# Main_Pyro.net
KiCad netlist of a schematic drawn in Altium Designer
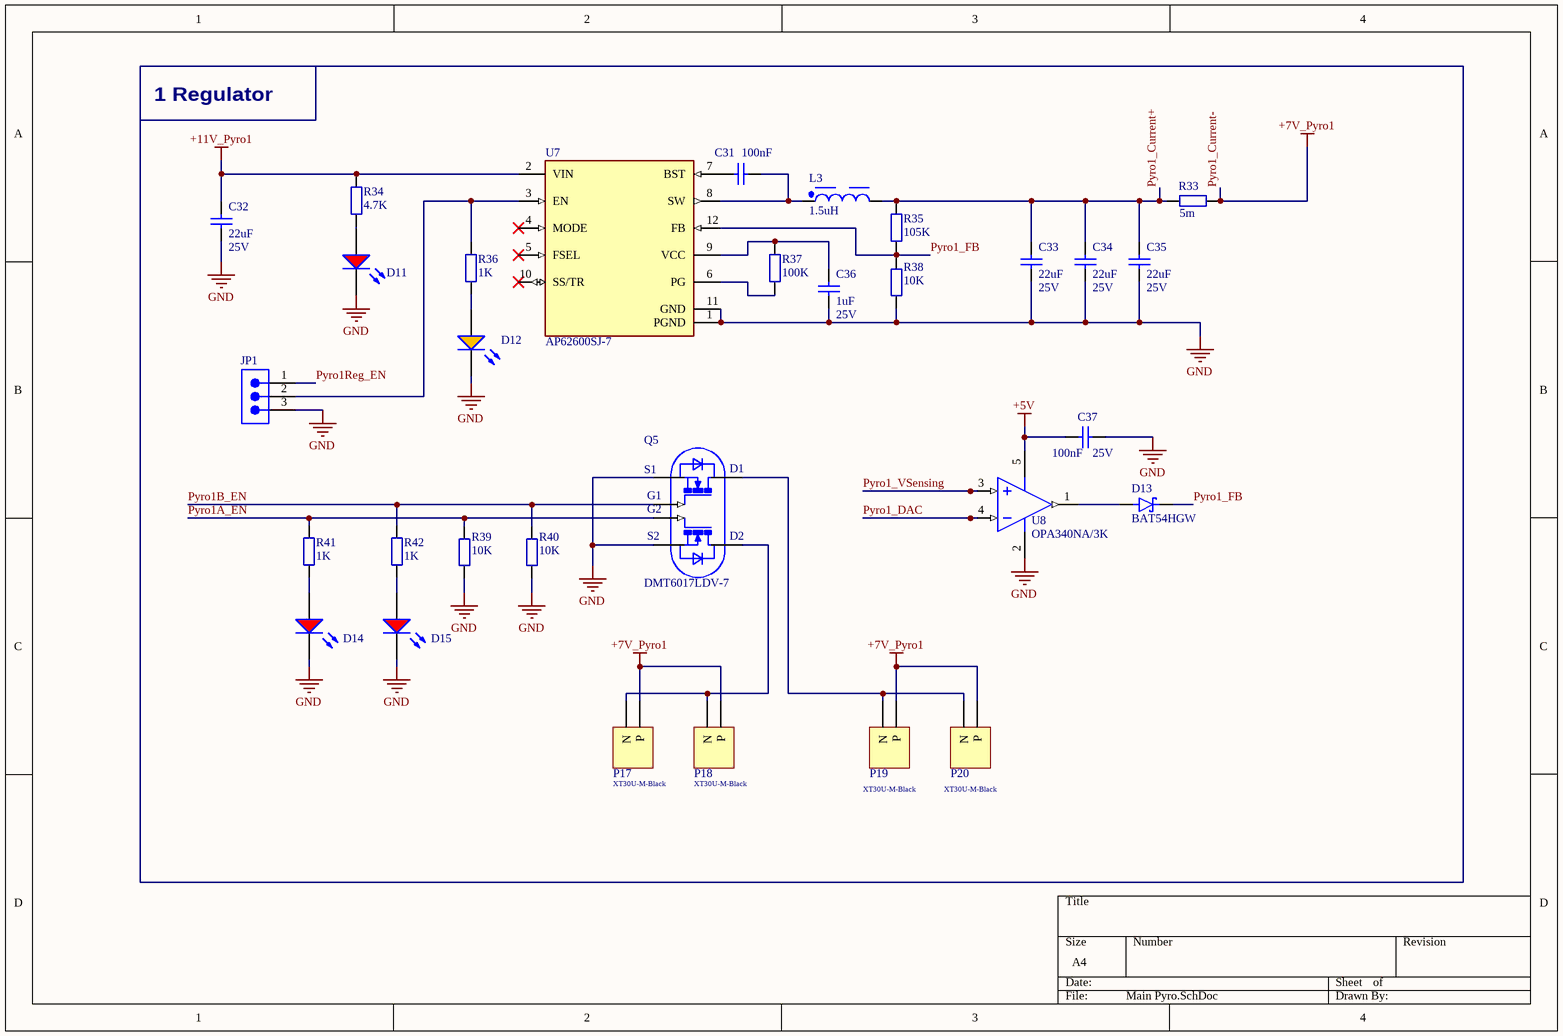
[diagram p0: Main Pyro.SchDoc]

(export (version "E")
  (design (tool "Eeschema 10.0.6"))
  (components
    (comp (ref "C31")
      (value "100nF")
      (footprint "MY_0603")
      (description "Capacitor, 100nF, 0603, 25V")
      (fields (field (name "VOLTAGE") "25V") (field (name "MANUFACTURER") "Wurth Elektronik"))
      (libsource (lib "LEEM UPM") (part "Cap ceramic"))
    )
    (comp (ref "C32")
      (value "22uF")
      (footprint "MY_0805")
      (description "Capacitor, 22uF, 0805, 25V")
      (fields
        (field (name "MANUFACTURER") "Samsung")
        (field (name "MANUFACTURER PART NUMBER") "CL21A226MAYNNNE")
        (field (name "VOLTAGE") "25V")
      )
      (libsource (lib "LEEM UPM") (part "Cap ceramic"))
    )
    (comp (ref "C33")
      (value "22uF")
      (footprint "MY_0805")
      (description "Capacitor, 22uF, 0805, 25V")
      (fields
        (field (name "MANUFACTURER") "Samsung")
        (field (name "MANUFACTURER PART NUMBER") "CL21A226MAYNNNE")
        (field (name "VOLTAGE") "25V")
      )
      (libsource (lib "LEEM UPM") (part "Cap ceramic"))
    )
    (comp (ref "C34")
      (value "22uF")
      (footprint "MY_0805")
      (description "Capacitor, 22uF, 0805, 25V")
      (fields
        (field (name "MANUFACTURER") "Samsung")
        (field (name "MANUFACTURER PART NUMBER") "CL21A226MAYNNNE")
        (field (name "VOLTAGE") "25V")
      )
      (libsource (lib "LEEM UPM") (part "Cap ceramic"))
    )
    (comp (ref "C35")
      (value "22uF")
      (footprint "MY_0805")
      (description "Capacitor, 22uF, 0805, 25V")
      (fields
        (field (name "MANUFACTURER") "Samsung")
        (field (name "MANUFACTURER PART NUMBER") "CL21A226MAYNNNE")
        (field (name "VOLTAGE") "25V")
      )
      (libsource (lib "LEEM UPM") (part "Cap ceramic"))
    )
    (comp (ref "C36")
      (value "1uF")
      (footprint "MY_0603")
      (description "Capacitor, 1uF, 0603, 25V")
      (fields
        (field (name "VOLTE") "25V")
        (field (name "MANUFACTURER") "Wurth Elektronik")
        (field (name "MANUFACTURER PART NUMBER") "885012206052")
      )
      (libsource (lib "LEEM UPM") (part "Cap ceramic"))
    )
    (comp (ref "C37")
      (value "100nF")
      (footprint "MY_0603")
      (description "Capacitor, 100nF, 0603, 25V")
      (fields
        (field (name "VOLTAGE") "25V")
        (field (name "MANUFACTURER") "Wurth Elektronik")
        (field (name "MANUFACTURER PART NUMBER") "885012206071")
      )
      (libsource (lib "LEEM UPM") (part "Cap ceramic"))
    )
    (comp (ref "D11")
      (value "150080RS75000")
      (footprint "WL-SMCW_0805_150080xx75000")
      (description "LED, 0805, Red")
      (fields (field (name "MANUFACTURER") "Wurth Elektronik"))
      (libsource (lib "Altium Content Vault") (part "LED_Red_2A-1K"))
    )
    (comp (ref "D12")
      (value "150080AS75000")
      (footprint "WL-SMCW_0805_150080xx75000")
      (description "LED, 0805, Amber")
      (fields (field (name "MANUFACTURER") "Wurth Elektronik"))
      (libsource (lib "Altium Content Vault") (part "LED_Amber_2A-1K"))
    )
    (comp (ref "D13")
      (value "BAT54HGW")
      (footprint "BAT54HGW-Footprint-1")
      (description "BAT54HGW Schotty Diode")
      (fields (field (name "MANUFACTURER") "Nexperia"))
      (libsource (lib "LEEM UPM") (part "BAT54HGW"))
    )
    (comp (ref "D14")
      (value "150080RS75000")
      (footprint "WL-SMCW_0805_150080xx75000")
      (fields (field (name "MANUFACTURER") "Wurth Elektronik"))
      (libsource (lib "Altium Content Vault") (part "LED_Red_2A-1K"))
    )
    (comp (ref "D15")
      (value "150080RS75000")
      (footprint "WL-SMCW_0805_150080xx75000")
      (fields (field (name "MANUFACTURER") "Wurth Elektronik"))
      (libsource (lib "Altium Content Vault") (part "LED_Red_2A-1K"))
    )
    (comp (ref "JP1")
      (value "Jumper 3 pin, 2,54mm")
      (footprint "Jumper 3 pin, 2,54mm-Footprint-1")
      (libsource (lib "LEEM UPM") (part "New symbol 1"))
    )
    (comp (ref "L3")
      (value "1.5uH")
      (footprint "WE-MAPI_4020")
      (description "74438356015 Fixed Ind 1.5UH 5.8A 19 Mohm SMD")
      (fields
        (field (name "MANUFACTURER") "Wurth Elektronik")
        (field (name "MANUFACTURER PART NUMBER") "74438356015")
      )
      (libsource (lib "Altium Content Vault") (part "Inductor - 2"))
    )
    (comp (ref "P17")
      (value "XT30U-M-Black")
      (footprint "XT30-Footprint-2")
      (description "XT30PW-M公头 Socket,DCsupply,XT30,male,PIN:2")
      (fields (field (name "MANUFACTURER") "AMASS"))
      (libsource (lib "LEEM UPM") (part "XT30PW"))
    )
    (comp (ref "P18")
      (value "XT30U-M-Black")
      (footprint "XT30-Footprint-2")
      (description "XT30PW-M公头 Socket,DCsupply,XT30,male,PIN:2")
      (fields (field (name "MANUFACTURER") "AMASS"))
      (libsource (lib "LEEM UPM") (part "XT30PW"))
    )
    (comp (ref "P19")
      (value "XT30U-M-Black")
      (footprint "XT30-Footprint-2")
      (description "XT30PW-M公头 Socket,DCsupply,XT30,male,PIN:2")
      (fields (field (name "MANUFACTURER") "AMASS"))
      (libsource (lib "LEEM UPM") (part "XT30PW"))
    )
    (comp (ref "P20")
      (value "XT30U-M-Black")
      (footprint "XT30-Footprint-2")
      (description "XT30PW-M公头 Socket,DCsupply,XT30,male,PIN:2")
      (fields (field (name "MANUFACTURER") "AMASS"))
      (libsource (lib "LEEM UPM") (part "XT30PW"))
    )
    (comp (ref "Q5")
      (value "DMT6017LDV-7")
      (footprint "DMT6017LDV-7-Footprint-1")
      (description "Small Signal Field-Effect Transistor")
      (libsource (lib "LEEM UPM") (part "DMT6017LDV"))
    )
    (comp (ref "R33")
      (value "5m")
      (footprint "R0612")
      (description "Resistor, 5m, 0612, 2W")
      (fields
        (field (name "MANUFACTURER") "Vishay")
        (field (name "MANUFACTURER PART NUMBER") "WFCP06125L000FE66")
      )
      (libsource (lib "LEEM UPM") (part "RK73H2ALTD1004F"))
    )
    (comp (ref "R34")
      (value "4.7K")
      (footprint "R0603-0.45")
      (description "Resistor, 4.7K, 0603, 0.1W")
      (fields (field (name "MANUFACTURER") "Wurth") (field (name "MANUFACTURER PART NUMBER") "560112116006"))
      (libsource (lib "LEEM UPM") (part "RK73H2ALTD1004F"))
    )
    (comp (ref "R35")
      (value "105K")
      (footprint "R0603-0.45")
      (description "Resistor, 105K, 0603, 0.1W")
      (fields (field (name "MANUFACTURER") "Wurth") (field (name "MANUFACTURER PART NUMBER") "560112110183"))
      (libsource (lib "IFS_Altium") (part "R"))
    )
    (comp (ref "R36")
      (value "1K")
      (footprint "R0603-0.45")
      (description "Resistor, 1K, 0603, 0.1W")
      (fields (field (name "MANUFACTURER") "Wurth") (field (name "MANUFACTURER PART NUMBER") "560112116014"))
      (libsource (lib "LEEM UPM") (part "RK73H2ALTD1004F"))
    )
    (comp (ref "R37")
      (value "100K")
      (footprint "R0603-0.45")
      (description "Resistor, 100K, 0603, 0.1W")
      (fields (field (name "MANUFACTURER") "Wurth") (field (name "MANUFACTURER PART NUMBER") "560112116004"))
      (libsource (lib "IFS_Altium") (part "R"))
    )
    (comp (ref "R38")
      (value "10K")
      (footprint "R0603-0.45")
      (description "Resistor, 10K, 0603, 0.1W")
      (fields
        (field (name "MANUFACTURER") "Vishay")
        (field (name "MANUFACTURER PART NUMBER") "RCS060310K0FKEA")
      )
      (libsource (lib "IFS_Altium") (part "R"))
    )
    (comp (ref "R39")
      (value "10K")
      (footprint "R0603-0.45")
      (description "Resistor, 10K, 0603, 0.1W")
      (fields
        (field (name "MANUFACTURER") "Vishay")
        (field (name "MANUFACTURER PART NUMBER") "RCS060310K0FKEA")
      )
      (libsource (lib "IFS_Altium") (part "R"))
    )
    (comp (ref "R40")
      (value "10K")
      (footprint "R0603-0.45")
      (description "Resistor, 10K, 0603, 0.1W")
      (fields
        (field (name "MANUFACTURER") "Vishay")
        (field (name "MANUFACTURER PART NUMBER") "RCS060310K0FKEA")
      )
      (libsource (lib "IFS_Altium") (part "R"))
    )
    (comp (ref "R41")
      (value "1K")
      (footprint "R0603-0.45")
      (description "Resistor, 1K, 0603, 0.1W")
      (fields (field (name "MANUFACTURER") "Wurth") (field (name "MANUFACTURER PART NUMBER") "560112116014"))
      (libsource (lib "LEEM UPM") (part "RK73H2ALTD1004F"))
    )
    (comp (ref "R42")
      (value "1K")
      (footprint "R0603-0.45")
      (description "Resistor, 1K, 0603, 0.1W")
      (fields (field (name "MANUFACTURER") "Wurth") (field (name "MANUFACTURER PART NUMBER") "560112116014"))
      (libsource (lib "LEEM UPM") (part "RK73H2ALTD1004F"))
    )
    (comp (ref "U7")
      (value "AP62600SJ-7")
      (footprint "FP-V-QFN2030-12_Type_A-MFG")
      (description "Switching Regulator, 1200kHz Switching Freq-Max")
      (fields (field (name "MANUFACTURER") "Diodes Incorporated"))
      (libsource (lib "LEEM UPM") (part "03c86ce2703f4b33b3045e94f7be521"))
    )
    (comp (ref "U8")
      (value "OPA340NA/3K")
      (footprint "DBV0005A_M")
      (fields (field (name "MANUFACTURER") "Texas Instruments"))
      (libsource (lib "Altium Content Vault") (part "TI-OPA_SM7XXXX-DBV5"))
    )
  )
  (nets
    (net (code "1") (name "+5V") (class "Default")
      (node (ref "C37") (pin "2") (pinfunction "2_2") (pintype "passive"))
      (node (ref "U8") (pin "5") (pinfunction "V+_5") (pintype "power_in"))
    )
    (net (code "2") (name "+7V_Pyro1") (class "Default")
      (node (ref "P17") (pin "P") (pinfunction "P_P") (pintype "passive"))
      (node (ref "P18") (pin "P") (pinfunction "P_P") (pintype "passive"))
      (node (ref "P19") (pin "P") (pinfunction "P_P") (pintype "passive"))
      (node (ref "P20") (pin "P") (pinfunction "P_P") (pintype "passive"))
      (node (ref "R33") (pin "2") (pinfunction "2_2") (pintype "passive"))
    )
    (net (code "3") (name "+11V_Pyro1") (class "Default")
      (node (ref "C32") (pin "1") (pinfunction "1_1") (pintype "passive"))
      (node (ref "R34") (pin "2") (pinfunction "2_2") (pintype "passive"))
      (node (ref "U7") (pin "2") (pinfunction "VIN_2") (pintype "power_in"))
    )
    (net (code "4") (name "/Pyro1A_EN") (class "Default")
      (node (ref "Q5") (pin "4") (pinfunction "G2_4") (pintype "input"))
      (node (ref "R39") (pin "1") (pinfunction "1_1") (pintype "passive"))
      (node (ref "R41") (pin "2") (pinfunction "2_2") (pintype "passive"))
    )
    (net (code "5") (name "/Pyro1B_EN") (class "Default")
      (node (ref "Q5") (pin "2") (pinfunction "G1_2") (pintype "input"))
      (node (ref "R40") (pin "1") (pinfunction "1_1") (pintype "passive"))
      (node (ref "R42") (pin "2") (pinfunction "2_2") (pintype "passive"))
    )
    (net (code "6") (name "/Pyro1Reg_EN") (class "Default")
      (node (ref "JP1") (pin "1") (pinfunction "1_1") (pintype "passive"))
    )
    (net (code "7") (name "/Pyro1_Current+") (class "Default")
      (node (ref "C33") (pin "1") (pinfunction "1_1") (pintype "passive"))
      (node (ref "C34") (pin "1") (pinfunction "1_1") (pintype "passive"))
      (node (ref "C35") (pin "1") (pinfunction "1_1") (pintype "passive"))
      (node (ref "L3") (pin "2") (pinfunction "2_2") (pintype "passive"))
      (node (ref "R33") (pin "1") (pinfunction "1_1") (pintype "passive"))
      (node (ref "R35") (pin "1") (pinfunction "1_1") (pintype "passive"))
    )
    (net (code "8") (name "/Pyro1_DAC") (class "Default")
      (node (ref "U8") (pin "4") (pinfunction "IN-_4") (pintype "input"))
    )
    (net (code "9") (name "/Pyro1_FB") (class "Default")
      (node (ref "D13") (pin "C") (pinfunction "K_C") (pintype "passive"))
      (node (ref "R35") (pin "2") (pinfunction "2_2") (pintype "passive"))
      (node (ref "R38") (pin "1") (pinfunction "1_1") (pintype "passive"))
      (node (ref "U7") (pin "12") (pinfunction "FB_12") (pintype "input"))
    )
    (net (code "10") (name "/Pyro1_VSensing") (class "Default")
      (node (ref "U8") (pin "3") (pinfunction "IN+_3") (pintype "input"))
    )
    (net (code "11") (name "GND") (class "Default")
      (node (ref "C32") (pin "2") (pinfunction "2_2") (pintype "passive"))
      (node (ref "C33") (pin "2") (pinfunction "2_2") (pintype "passive"))
      (node (ref "C34") (pin "2") (pinfunction "2_2") (pintype "passive"))
      (node (ref "C35") (pin "2") (pinfunction "2_2") (pintype "passive"))
      (node (ref "C36") (pin "1") (pinfunction "1_1") (pintype "passive"))
      (node (ref "C37") (pin "1") (pinfunction "1_1") (pintype "passive"))
      (node (ref "D11") (pin "1") (pinfunction "K_1") (pintype "passive"))
      (node (ref "D12") (pin "1") (pinfunction "K_1") (pintype "passive"))
      (node (ref "D14") (pin "1") (pinfunction "K_1") (pintype "passive"))
      (node (ref "D15") (pin "1") (pinfunction "K_1") (pintype "passive"))
      (node (ref "JP1") (pin "3") (pinfunction "3_3") (pintype "passive"))
      (node (ref "Q5") (pin "1") (pinfunction "S1_1") (pintype "power_in"))
      (node (ref "Q5") (pin "3") (pinfunction "S2_3") (pintype "power_in"))
      (node (ref "R38") (pin "2") (pinfunction "2_2") (pintype "passive"))
      (node (ref "R39") (pin "2") (pinfunction "2_2") (pintype "passive"))
      (node (ref "R40") (pin "2") (pinfunction "2_2") (pintype "passive"))
      (node (ref "U7") (pin "1") (pinfunction "PGND_1") (pintype "power_in"))
      (node (ref "U7") (pin "11") (pinfunction "GND_11") (pintype "power_in"))
      (node (ref "U8") (pin "2") (pinfunction "V-_2") (pintype "power_in"))
    )
    (net (code "12") (name "Net-(D11-A)") (class "Default")
      (node (ref "D11") (pin "2") (pinfunction "A_2") (pintype "passive"))
      (node (ref "R34") (pin "1") (pinfunction "1_1") (pintype "passive"))
    )
    (net (code "13") (name "Net-(D12-A)") (class "Default")
      (node (ref "D12") (pin "2") (pinfunction "A_2") (pintype "passive"))
      (node (ref "R36") (pin "1") (pinfunction "1_1") (pintype "passive"))
    )
    (net (code "14") (name "Net-(D14-A)") (class "Default")
      (node (ref "D14") (pin "2") (pinfunction "A_2") (pintype "passive"))
      (node (ref "R41") (pin "1") (pinfunction "1_1") (pintype "passive"))
    )
    (net (code "15") (name "Net-(D15-A)") (class "Default")
      (node (ref "D15") (pin "2") (pinfunction "A_2") (pintype "passive"))
      (node (ref "R42") (pin "1") (pinfunction "1_1") (pintype "passive"))
    )
    (net (code "16") (name "Net-(Q5-D1)") (class "Default")
      (node (ref "P19") (pin "N") (pinfunction "N_N") (pintype "passive"))
      (node (ref "P20") (pin "N") (pinfunction "N_N") (pintype "passive"))
      (node (ref "Q5") (pin "8") (pinfunction "D1_8") (pintype "power_in"))
    )
    (net (code "17") (name "Net-(Q5-D2)") (class "Default")
      (node (ref "P17") (pin "N") (pinfunction "N_N") (pintype "passive"))
      (node (ref "P18") (pin "N") (pinfunction "N_N") (pintype "passive"))
      (node (ref "Q5") (pin "6") (pinfunction "D2_6") (pintype "power_in"))
    )
    (net (code "18") (name "Net-(U7-BST)") (class "Default")
      (node (ref "C31") (pin "2") (pinfunction "2_2") (pintype "passive"))
      (node (ref "U7") (pin "7") (pinfunction "BST_7") (pintype "input"))
    )
    (net (code "19") (name "Net-(U7-EN)") (class "Default")
      (node (ref "JP1") (pin "2") (pinfunction "2_2") (pintype "passive"))
      (node (ref "R36") (pin "2") (pinfunction "2_2") (pintype "passive"))
      (node (ref "U7") (pin "3") (pinfunction "EN_3") (pintype "input"))
    )
    (net (code "20") (name "Net-(U7-PG)") (class "Default")
      (node (ref "R37") (pin "2") (pinfunction "2_2") (pintype "passive"))
      (node (ref "U7") (pin "6") (pinfunction "PG_6") (pintype "open_collector"))
    )
    (net (code "21") (name "Net-(U7-SW)") (class "Default")
      (node (ref "C31") (pin "1") (pinfunction "1_1") (pintype "passive"))
      (node (ref "L3") (pin "1") (pinfunction "1_1") (pintype "passive"))
      (node (ref "U7") (pin "8") (pinfunction "SW_8") (pintype "output"))
    )
    (net (code "22") (name "Net-(U7-VCC)") (class "Default")
      (node (ref "C36") (pin "2") (pinfunction "2_2") (pintype "passive"))
      (node (ref "R37") (pin "1") (pinfunction "1_1") (pintype "passive"))
      (node (ref "U7") (pin "9") (pinfunction "VCC_9") (pintype "power_in"))
    )
    (net (code "23") (name "Net-(U8-OUT)") (class "Default")
      (node (ref "D13") (pin "A") (pinfunction "A_A") (pintype "passive"))
      (node (ref "U8") (pin "1") (pinfunction "OUT_1") (pintype "output"))
    )
    (net (code "24") (name "unconnected-(U7-FSEL-Pad5)") (class "Default")
      (node (ref "U7") (pin "5") (pinfunction "FSEL_5") (pintype "input+no_connect"))
    )
    (net (code "25") (name "unconnected-(U7-MODE-Pad4)") (class "Default")
      (node (ref "U7") (pin "4") (pinfunction "MODE_4") (pintype "input+no_connect"))
    )
    (net (code "26") (name "unconnected-(U7-SS{slash}TR-Pad10)") (class "Default")
      (node (ref "U7") (pin "10") (pinfunction "SS/TR_10") (pintype "bidirectional+no_connect"))
    )
  )
)
